# nrf52840_four_input_minew_module_v01.net
KiCad netlist of a schematic drawn in EAGLE
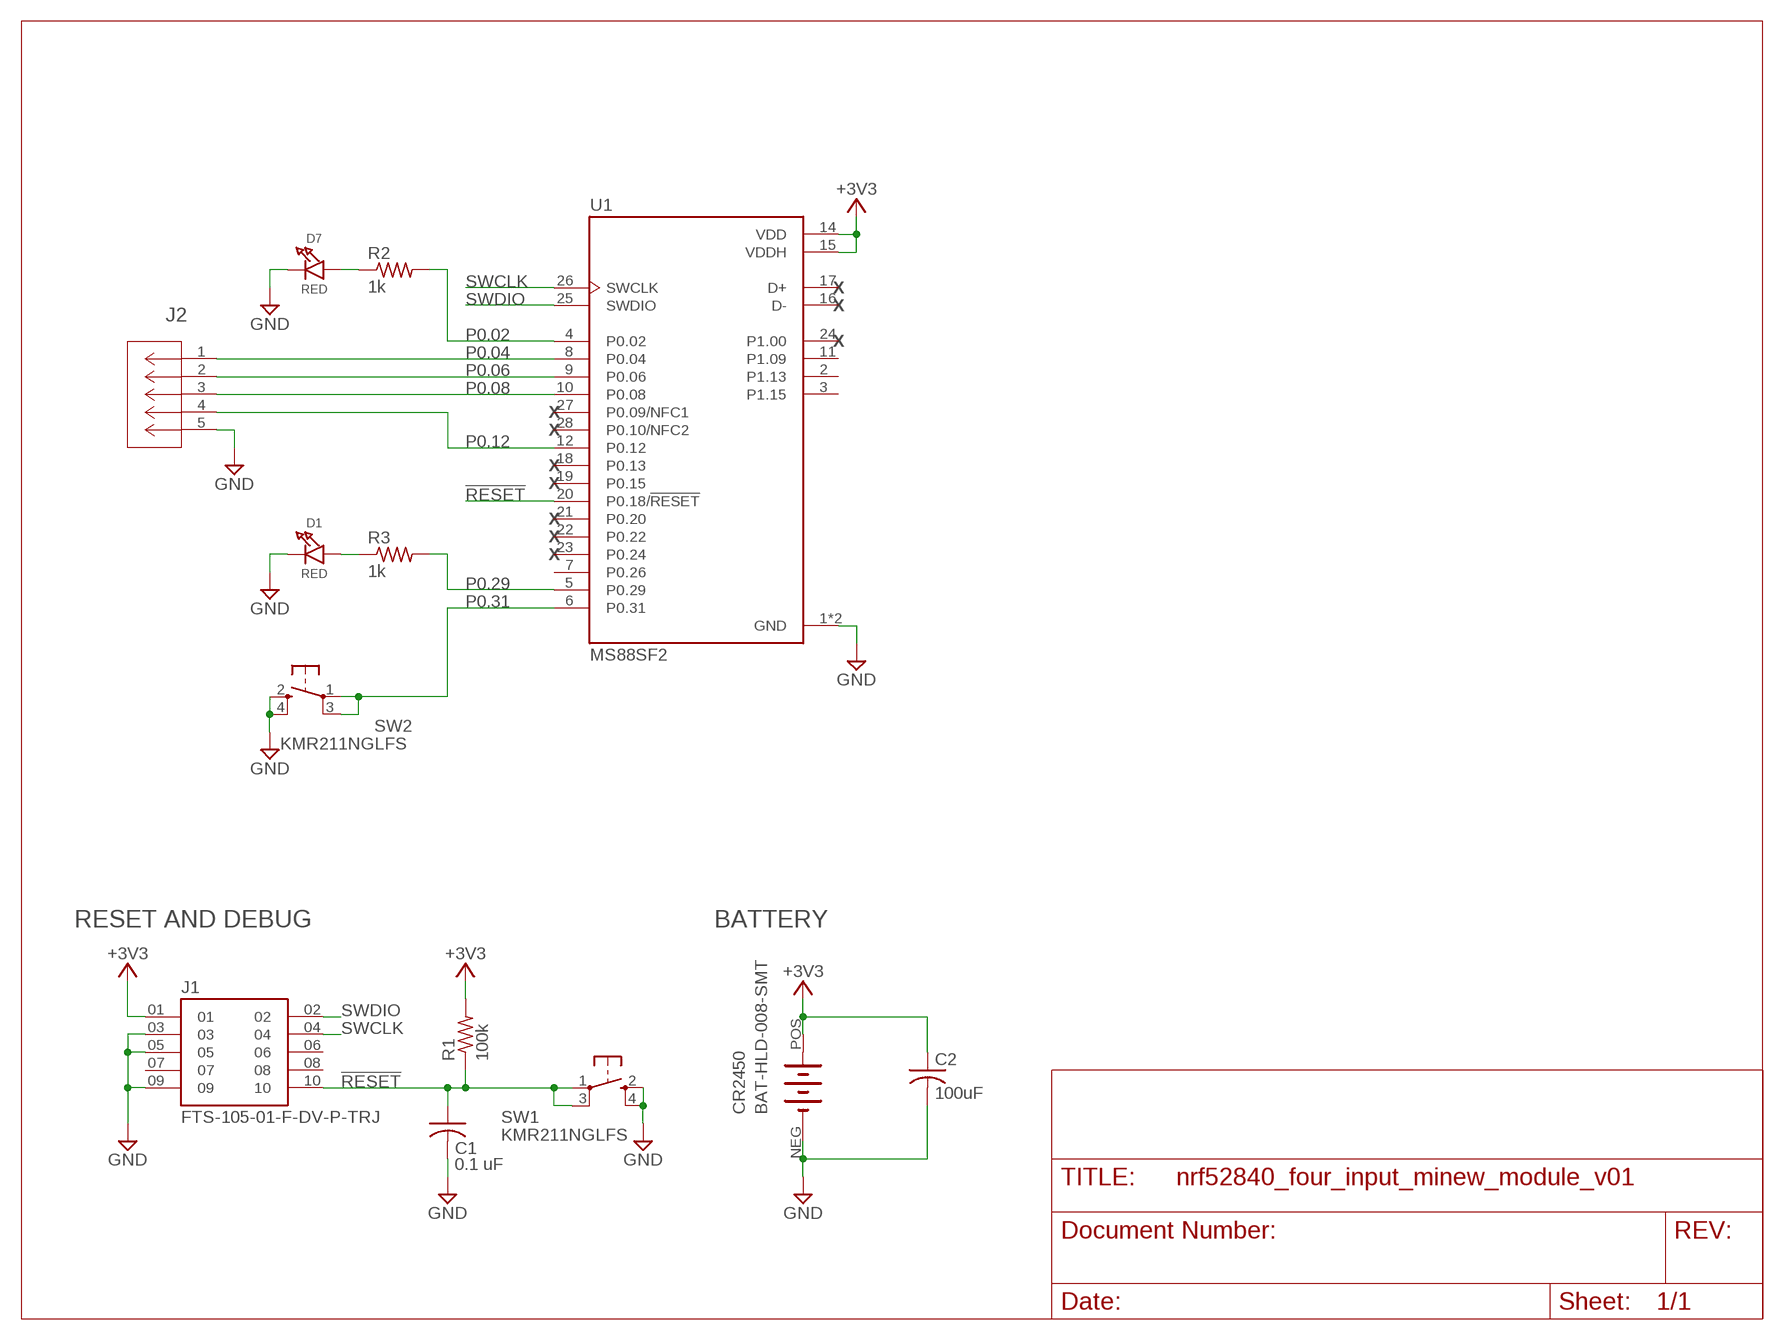
[diagram p0: schematic, sheet 1]

(export (version "E")
  (design (tool "Eeschema 10.0.6"))
  (components
    (comp (ref "C1")
      (value "0.1 uF")
      (footprint "eagle-import:C0603K")
      (libsource (lib "eagle-import") (part "C-USC0603K"))
    )
    (comp (ref "C2")
      (value "100uF")
      (footprint "eagle-import:C1210K")
      (libsource (lib "eagle-import") (part "C-USC1210K"))
    )
    (comp (ref "CR2450")
      (value "BAT-HLD-008-SMT")
      (footprint "eagle-import:BAT-HLD-008-SMT")
      (libsource (lib "eagle-import") (part "BAT-HLD-008-SMT"))
    )
    (comp (ref "D1")
      (value "RED")
      (footprint "eagle-import:CHIPLED_0805_NOOUTLINE")
      (libsource (lib "eagle-import") (part "LED0805_NOOUTLINE"))
    )
    (comp (ref "D7")
      (value "RED")
      (footprint "eagle-import:CHIPLED_0805_NOOUTLINE")
      (libsource (lib "eagle-import") (part "LED0805_NOOUTLINE"))
    )
    (comp (ref "J1")
      (value "FTS-105-01-F-DV-P-TRJ")
      (footprint "eagle-import:SAMTEC_FTS-105-01-F-DV-P-TR")
      (fields (field (name "MF") "Samtec") (field (name "MP") "FTS-105-01-F-DV-P-TR"))
      (libsource (lib "eagle-import") (part "FTS-105-01-F-DV-P-TRJ"))
    )
    (comp (ref "J2")
      (value "1725685")
      (footprint "eagle-import:CONN_1725685_PXC")
      (fields (field (name "COPYRIGHT") "Copyright (C) 2024 Ultra Librarian. All rights reserved."))
      (libsource (lib "eagle-import") (part "1725685"))
    )
    (comp (ref "R1")
      (value "100k")
      (footprint "eagle-import:R0603")
      (libsource (lib "eagle-import") (part "R-US_R0603"))
    )
    (comp (ref "R2")
      (value "1k")
      (footprint "eagle-import:R0603")
      (libsource (lib "eagle-import") (part "R-US_R0603"))
    )
    (comp (ref "R3")
      (value "1k")
      (footprint "eagle-import:R0603")
      (libsource (lib "eagle-import") (part "R-US_R0603"))
    )
    (comp (ref "SW1")
      (value "KMR211NGLFS")
      (footprint "eagle-import:KMR2")
      (libsource (lib "eagle-import") (part "SPST_TACT-KMR2"))
    )
    (comp (ref "SW2")
      (value "KMR211NGLFS")
      (footprint "eagle-import:KMR2")
      (libsource (lib "eagle-import") (part "SPST_TACT-KMR2"))
    )
    (comp (ref "U1")
      (value "MS88SF2")
      (footprint "eagle-import:XCVR_MS88SF2")
      (fields (field (name "MF") "Minew"))
      (libsource (lib "eagle-import") (part "MS88SF2"))
    )
  )
  (nets
    (net (code "1") (name "+3V3") (class "Default")
      (node (ref "C2") (pin "1") (pinfunction "1_1") (pintype "passive"))
      (node (ref "CR2450") (pin "POS") (pinfunction "+_POS") (pintype "passive"))
      (node (ref "J1") (pin "01") (pinfunction "01_01") (pintype "passive"))
      (node (ref "R1") (pin "2") (pinfunction "2_2") (pintype "passive"))
      (node (ref "U1") (pin "14") (pinfunction "VDD_14") (pintype "power_in"))
      (node (ref "U1") (pin "15") (pinfunction "VDDH_15") (pintype "power_in"))
    )
    (net (code "2") (name "/P0.02") (class "Default")
      (node (ref "R2") (pin "2") (pinfunction "2_2") (pintype "passive"))
      (node (ref "U1") (pin "4") (pinfunction "P0.02_4") (pintype "bidirectional"))
    )
    (net (code "3") (name "/P0.04") (class "Default")
      (node (ref "J2") (pin "1") (pinfunction "1_1") (pintype "passive"))
      (node (ref "U1") (pin "8") (pinfunction "P0.04_8") (pintype "bidirectional"))
    )
    (net (code "4") (name "/P0.06") (class "Default")
      (node (ref "J2") (pin "2") (pinfunction "2_2") (pintype "passive"))
      (node (ref "U1") (pin "9") (pinfunction "P0.06_9") (pintype "bidirectional"))
    )
    (net (code "5") (name "/P0.08") (class "Default")
      (node (ref "J2") (pin "3") (pinfunction "3_3") (pintype "passive"))
      (node (ref "U1") (pin "10") (pinfunction "P0.08_10") (pintype "bidirectional"))
    )
    (net (code "6") (name "/P0.12") (class "Default")
      (node (ref "J2") (pin "4") (pinfunction "4_4") (pintype "passive"))
      (node (ref "U1") (pin "12") (pinfunction "P0.12_12") (pintype "bidirectional"))
    )
    (net (code "7") (name "/P0.29") (class "Default")
      (node (ref "R3") (pin "2") (pinfunction "2_2") (pintype "passive"))
      (node (ref "U1") (pin "5") (pinfunction "P0.29_5") (pintype "bidirectional"))
    )
    (net (code "8") (name "/P0.31") (class "Default")
      (node (ref "SW2") (pin "1") (pinfunction "P_1") (pintype "passive"))
      (node (ref "SW2") (pin "3") (pinfunction "P1_3") (pintype "passive"))
      (node (ref "U1") (pin "6") (pinfunction "P0.31_6") (pintype "bidirectional"))
    )
    (net (code "9") (name "/SWCLK") (class "Default")
      (node (ref "J1") (pin "04") (pinfunction "04_04") (pintype "passive"))
      (node (ref "U1") (pin "26") (pinfunction "SWCLK_26") (pintype "input"))
    )
    (net (code "10") (name "/SWDIO") (class "Default")
      (node (ref "J1") (pin "02") (pinfunction "02_02") (pintype "passive"))
      (node (ref "U1") (pin "25") (pinfunction "SWDIO_25") (pintype "bidirectional"))
    )
    (net (code "11") (name "/~{RESET}") (class "Default")
      (node (ref "C1") (pin "1") (pinfunction "1_1") (pintype "passive"))
      (node (ref "J1") (pin "10") (pinfunction "10_10") (pintype "passive"))
      (node (ref "R1") (pin "1") (pinfunction "1_1") (pintype "passive"))
      (node (ref "SW1") (pin "1") (pinfunction "P_1") (pintype "passive"))
      (node (ref "SW1") (pin "3") (pinfunction "P1_3") (pintype "passive"))
      (node (ref "U1") (pin "20") (pinfunction "P0.18/~{RESET}_20") (pintype "bidirectional"))
    )
    (net (code "12") (name "GND") (class "Default")
      (node (ref "C1") (pin "2") (pinfunction "2_2") (pintype "passive"))
      (node (ref "C2") (pin "2") (pinfunction "2_2") (pintype "passive"))
      (node (ref "CR2450") (pin "NEG") (pinfunction "-_NEG") (pintype "passive"))
      (node (ref "D1") (pin "C") (pinfunction "C_C") (pintype "passive"))
      (node (ref "D7") (pin "C") (pinfunction "C_C") (pintype "passive"))
      (node (ref "J1") (pin "03") (pinfunction "03_03") (pintype "passive"))
      (node (ref "J1") (pin "05") (pinfunction "05_05") (pintype "passive"))
      (node (ref "J1") (pin "09") (pinfunction "09_09") (pintype "passive"))
      (node (ref "J2") (pin "5") (pinfunction "5_5") (pintype "passive"))
      (node (ref "SW1") (pin "2") (pinfunction "S_2") (pintype "passive"))
      (node (ref "SW1") (pin "4") (pinfunction "S1_4") (pintype "passive"))
      (node (ref "SW2") (pin "2") (pinfunction "S_2") (pintype "passive"))
      (node (ref "SW2") (pin "4") (pinfunction "S1_4") (pintype "passive"))
      (node (ref "U1") (pin "1") (pinfunction "GND_1") (pintype "power_in"))
      (node (ref "U1") (pin "13") (pinfunction "GND_13") (pintype "power_in"))
    )
    (net (code "13") (name "Net-(D1-PadA)") (class "Default")
      (node (ref "D1") (pin "A") (pinfunction "A_A") (pintype "passive"))
      (node (ref "R3") (pin "1") (pinfunction "1_1") (pintype "passive"))
    )
    (net (code "14") (name "Net-(D7-PadA)") (class "Default")
      (node (ref "D7") (pin "A") (pinfunction "A_A") (pintype "passive"))
      (node (ref "R2") (pin "1") (pinfunction "1_1") (pintype "passive"))
    )
    (net (code "15") (name "unconnected-(J1-Pad06)") (class "Default")
      (node (ref "J1") (pin "06") (pinfunction "06_06") (pintype "passive"))
    )
    (net (code "16") (name "unconnected-(J1-Pad07)") (class "Default")
      (node (ref "J1") (pin "07") (pinfunction "07_07") (pintype "passive"))
    )
    (net (code "17") (name "unconnected-(J1-Pad08)") (class "Default")
      (node (ref "J1") (pin "08") (pinfunction "08_08") (pintype "passive"))
    )
    (net (code "18") (name "unconnected-(U1-D+-Pad17)") (class "Default")
      (node (ref "U1") (pin "17") (pinfunction "D+_17") (pintype "bidirectional"))
    )
    (net (code "19") (name "unconnected-(U1-D--Pad16)") (class "Default")
      (node (ref "U1") (pin "16") (pinfunction "D-_16") (pintype "bidirectional"))
    )
    (net (code "20") (name "unconnected-(U1-P0.09{slash}NFC1-Pad27)") (class "Default")
      (node (ref "U1") (pin "27") (pinfunction "P0.09/NFC1_27") (pintype "bidirectional"))
    )
    (net (code "21") (name "unconnected-(U1-P0.10{slash}NFC2-Pad28)") (class "Default")
      (node (ref "U1") (pin "28") (pinfunction "P0.10/NFC2_28") (pintype "bidirectional"))
    )
    (net (code "22") (name "unconnected-(U1-P0.13-Pad18)") (class "Default")
      (node (ref "U1") (pin "18") (pinfunction "P0.13_18") (pintype "bidirectional"))
    )
    (net (code "23") (name "unconnected-(U1-P0.15-Pad19)") (class "Default")
      (node (ref "U1") (pin "19") (pinfunction "P0.15_19") (pintype "bidirectional"))
    )
    (net (code "24") (name "unconnected-(U1-P0.20-Pad21)") (class "Default")
      (node (ref "U1") (pin "21") (pinfunction "P0.20_21") (pintype "bidirectional"))
    )
    (net (code "25") (name "unconnected-(U1-P0.22-Pad22)") (class "Default")
      (node (ref "U1") (pin "22") (pinfunction "P0.22_22") (pintype "bidirectional"))
    )
    (net (code "26") (name "unconnected-(U1-P0.24-Pad23)") (class "Default")
      (node (ref "U1") (pin "23") (pinfunction "P0.24_23") (pintype "bidirectional"))
    )
    (net (code "27") (name "unconnected-(U1-P0.26-Pad7)") (class "Default")
      (node (ref "U1") (pin "7") (pinfunction "P0.26_7") (pintype "bidirectional"))
    )
    (net (code "28") (name "unconnected-(U1-P1.00-Pad24)") (class "Default")
      (node (ref "U1") (pin "24") (pinfunction "P1.00_24") (pintype "bidirectional"))
    )
    (net (code "29") (name "unconnected-(U1-P1.09-Pad11)") (class "Default")
      (node (ref "U1") (pin "11") (pinfunction "P1.09_11") (pintype "bidirectional"))
    )
    (net (code "30") (name "unconnected-(U1-P1.13-Pad2)") (class "Default")
      (node (ref "U1") (pin "2") (pinfunction "P1.13_2") (pintype "bidirectional"))
    )
    (net (code "31") (name "unconnected-(U1-P1.15-Pad3)") (class "Default")
      (node (ref "U1") (pin "3") (pinfunction "P1.15_3") (pintype "bidirectional"))
    )
  )
)
